# placa_4sensores_Certa.net
KiCad netlist of a schematic drawn in EAGLE
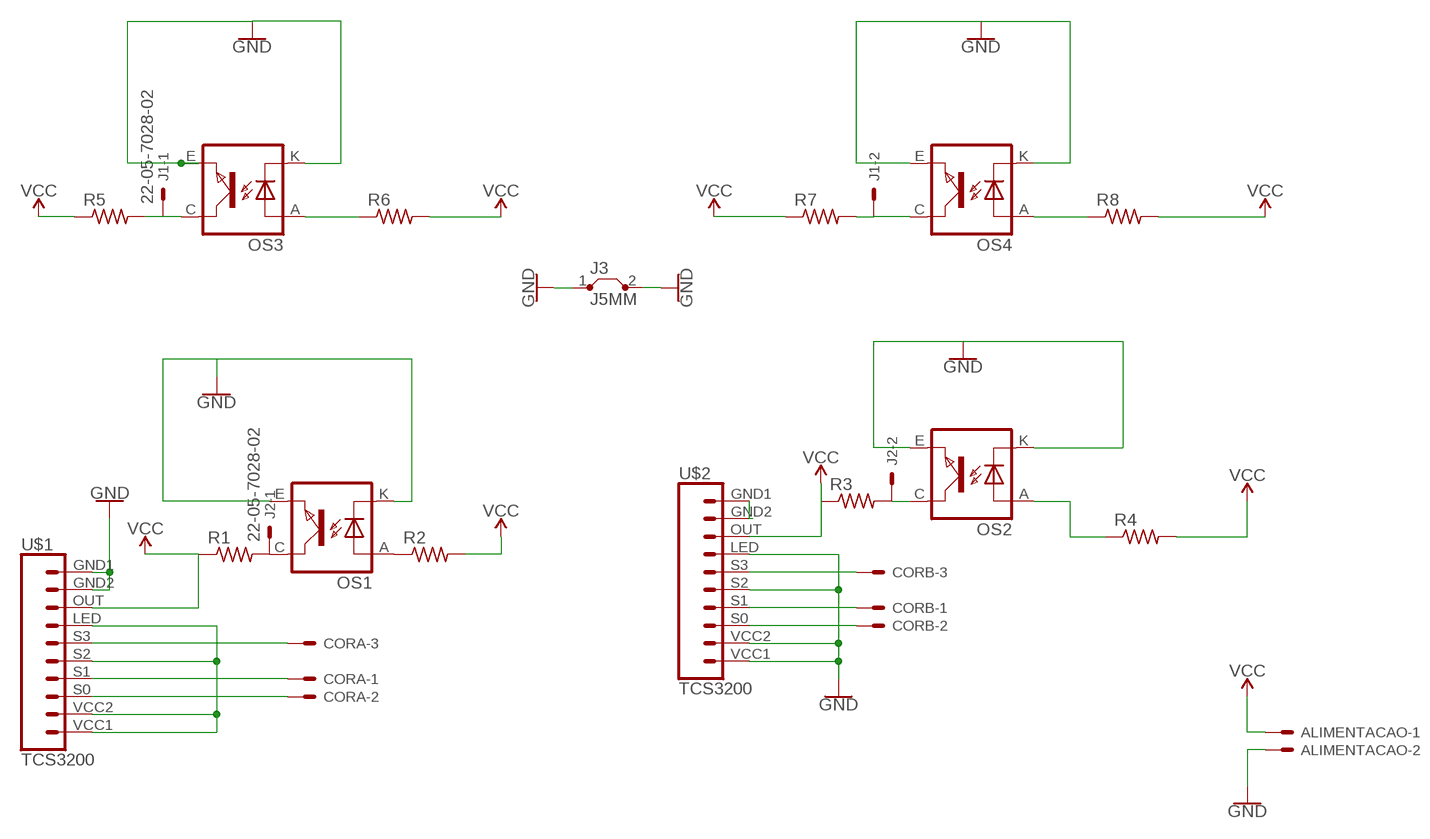
[diagram p0: schematic, sheet 1]

(export (version "E")
  (design (tool "Eeschema 10.0.6"))
  (components
    (comp (ref "ALIMENTACAO")
      (value "22-05-7028-02")
      (footprint "eagle-import:7395-02")
      (libsource (lib "eagle-import") (part "22-?-0205-7028"))
    )
    (comp (ref "CORA")
      (value "22-05-7038-03")
      (footprint "eagle-import:7395-03")
      (libsource (lib "eagle-import") (part "22-?-0305-7038"))
    )
    (comp (ref "CORB")
      (value "22-05-7038-03")
      (footprint "eagle-import:7395-03")
      (libsource (lib "eagle-import") (part "22-?-0305-7038"))
    )
    (comp (ref "J1")
      (value "22-05-7028-02")
      (footprint "eagle-import:7395-02")
      (libsource (lib "eagle-import") (part "22-?-0205-7028"))
    )
    (comp (ref "J2")
      (value "22-05-7028-02")
      (footprint "eagle-import:7395-02")
      (libsource (lib "eagle-import") (part "22-?-0205-7028"))
    )
    (comp (ref "J3")
      (value "J5MM")
      (footprint "eagle-import:05")
      (libsource (lib "eagle-import") (part "J5MM"))
    )
    (comp (ref "OS1")
      (value "TCRT5000")
      (footprint "eagle-import:TCRT5000")
      (libsource (lib "eagle-import") (part "TCRT5000"))
    )
    (comp (ref "OS2")
      (value "TCRT5000")
      (footprint "eagle-import:TCRT5000")
      (libsource (lib "eagle-import") (part "TCRT5000"))
    )
    (comp (ref "OS3")
      (value "TCRT5000")
      (footprint "eagle-import:TCRT5000")
      (libsource (lib "eagle-import") (part "TCRT5000"))
    )
    (comp (ref "OS4")
      (value "TCRT5000")
      (footprint "eagle-import:TCRT5000")
      (libsource (lib "eagle-import") (part "TCRT5000"))
    )
    (comp (ref "R1")
      (value "R-US_0204/5")
      (footprint "eagle-import:0204_5")
      (libsource (lib "eagle-import") (part "R-US_0204/5"))
    )
    (comp (ref "R2")
      (value "R-US_0204/5")
      (footprint "eagle-import:0204_5")
      (libsource (lib "eagle-import") (part "R-US_0204/5"))
    )
    (comp (ref "R3")
      (value "R-US_0204/5")
      (footprint "eagle-import:0204_5")
      (libsource (lib "eagle-import") (part "R-US_0204/5"))
    )
    (comp (ref "R4")
      (value "R-US_0204/5")
      (footprint "eagle-import:0204_5")
      (libsource (lib "eagle-import") (part "R-US_0204/5"))
    )
    (comp (ref "R5")
      (value "R-US_0204/5")
      (footprint "eagle-import:0204_5")
      (libsource (lib "eagle-import") (part "R-US_0204/5"))
    )
    (comp (ref "R6")
      (value "R-US_0204/5")
      (footprint "eagle-import:0204_5")
      (libsource (lib "eagle-import") (part "R-US_0204/5"))
    )
    (comp (ref "R7")
      (value "R-US_0204/5")
      (footprint "eagle-import:0204_5")
      (libsource (lib "eagle-import") (part "R-US_0204/5"))
    )
    (comp (ref "R8")
      (value "R-US_0204/5")
      (footprint "eagle-import:0204_5")
      (libsource (lib "eagle-import") (part "R-US_0204/5"))
    )
    (comp (ref "U$1")
      (value "TCS3200")
      (footprint "eagle-import:TCS3200")
      (libsource (lib "eagle-import") (part "TCS3200"))
    )
    (comp (ref "U$2")
      (value "TCS3200")
      (footprint "eagle-import:TCS3200")
      (libsource (lib "eagle-import") (part "TCS3200"))
    )
  )
  (nets
    (net (code "1") (name "GND") (class "Default")
      (node (ref "ALIMENTACAO") (pin "2") (pinfunction "S_2") (pintype "passive"))
      (node (ref "J3") (pin "1") (pinfunction "1_1") (pintype "passive"))
      (node (ref "J3") (pin "2") (pinfunction "2_2") (pintype "passive"))
      (node (ref "OS1") (pin "E") (pinfunction "EMITTER_E") (pintype "passive"))
      (node (ref "OS1") (pin "K") (pinfunction "CATHODE_K") (pintype "passive"))
      (node (ref "OS2") (pin "E") (pinfunction "EMITTER_E") (pintype "passive"))
      (node (ref "OS2") (pin "K") (pinfunction "CATHODE_K") (pintype "passive"))
      (node (ref "OS3") (pin "E") (pinfunction "EMITTER_E") (pintype "passive"))
      (node (ref "OS3") (pin "K") (pinfunction "CATHODE_K") (pintype "passive"))
      (node (ref "OS4") (pin "E") (pinfunction "EMITTER_E") (pintype "passive"))
      (node (ref "OS4") (pin "K") (pinfunction "CATHODE_K") (pintype "passive"))
      (node (ref "U$1") (pin "GND1") (pinfunction "GND1_GND1") (pintype "passive"))
      (node (ref "U$1") (pin "GND2") (pinfunction "GND2_GND2") (pintype "passive"))
      (node (ref "U$2") (pin "LED") (pinfunction "LED_LED") (pintype "passive"))
      (node (ref "U$2") (pin "S2") (pinfunction "S2_S2") (pintype "passive"))
      (node (ref "U$2") (pin "VCC1") (pinfunction "VCC1_VCC1") (pintype "passive"))
      (node (ref "U$2") (pin "VCC2") (pinfunction "VCC2_VCC2") (pintype "passive"))
    )
    (net (code "2") (name "Net-(CORAA-S)") (class "Default")
      (node (ref "CORA") (pin "1") (pinfunction "S_1") (pintype "passive"))
      (node (ref "U$1") (pin "S1") (pinfunction "S1_S1") (pintype "passive"))
    )
    (net (code "3") (name "Net-(CORAB-S)") (class "Default")
      (node (ref "CORA") (pin "2") (pinfunction "S_2") (pintype "passive"))
      (node (ref "U$1") (pin "S0") (pinfunction "S0_S0") (pintype "passive"))
    )
    (net (code "4") (name "Net-(CORAC-S)") (class "Default")
      (node (ref "CORA") (pin "3") (pinfunction "S_3") (pintype "passive"))
      (node (ref "U$1") (pin "S3") (pinfunction "S3_S3") (pintype "passive"))
    )
    (net (code "5") (name "Net-(CORBA-S)") (class "Default")
      (node (ref "CORB") (pin "1") (pinfunction "S_1") (pintype "passive"))
      (node (ref "U$2") (pin "S1") (pinfunction "S1_S1") (pintype "passive"))
    )
    (net (code "6") (name "Net-(CORBB-S)") (class "Default")
      (node (ref "CORB") (pin "2") (pinfunction "S_2") (pintype "passive"))
      (node (ref "U$2") (pin "S0") (pinfunction "S0_S0") (pintype "passive"))
    )
    (net (code "7") (name "Net-(CORBC-S)") (class "Default")
      (node (ref "CORB") (pin "3") (pinfunction "S_3") (pintype "passive"))
      (node (ref "U$2") (pin "S3") (pinfunction "S3_S3") (pintype "passive"))
    )
    (net (code "8") (name "Net-(J1A-S)") (class "Default")
      (node (ref "J1") (pin "1") (pinfunction "S_1") (pintype "passive"))
      (node (ref "OS3") (pin "C") (pinfunction "COLLECTOR_C") (pintype "passive"))
      (node (ref "R5") (pin "2") (pinfunction "2_2") (pintype "passive"))
    )
    (net (code "9") (name "Net-(J1B-S)") (class "Default")
      (node (ref "J1") (pin "2") (pinfunction "S_2") (pintype "passive"))
      (node (ref "OS4") (pin "C") (pinfunction "COLLECTOR_C") (pintype "passive"))
      (node (ref "R7") (pin "2") (pinfunction "2_2") (pintype "passive"))
    )
    (net (code "10") (name "Net-(J2A-S)") (class "Default")
      (node (ref "J2") (pin "1") (pinfunction "S_1") (pintype "passive"))
      (node (ref "OS1") (pin "C") (pinfunction "COLLECTOR_C") (pintype "passive"))
      (node (ref "R1") (pin "2") (pinfunction "2_2") (pintype "passive"))
    )
    (net (code "11") (name "Net-(J2B-S)") (class "Default")
      (node (ref "J2") (pin "2") (pinfunction "S_2") (pintype "passive"))
      (node (ref "OS2") (pin "C") (pinfunction "COLLECTOR_C") (pintype "passive"))
      (node (ref "R3") (pin "2") (pinfunction "2_2") (pintype "passive"))
    )
    (net (code "12") (name "Net-(OS1-ANODE)") (class "Default")
      (node (ref "OS1") (pin "A") (pinfunction "ANODE_A") (pintype "passive"))
      (node (ref "R2") (pin "1") (pinfunction "1_1") (pintype "passive"))
    )
    (net (code "13") (name "Net-(OS2-ANODE)") (class "Default")
      (node (ref "OS2") (pin "A") (pinfunction "ANODE_A") (pintype "passive"))
      (node (ref "R4") (pin "1") (pinfunction "1_1") (pintype "passive"))
    )
    (net (code "14") (name "Net-(OS3-ANODE)") (class "Default")
      (node (ref "OS3") (pin "A") (pinfunction "ANODE_A") (pintype "passive"))
      (node (ref "R6") (pin "1") (pinfunction "1_1") (pintype "passive"))
    )
    (net (code "15") (name "Net-(OS4-ANODE)") (class "Default")
      (node (ref "OS4") (pin "A") (pinfunction "ANODE_A") (pintype "passive"))
      (node (ref "R8") (pin "1") (pinfunction "1_1") (pintype "passive"))
    )
    (net (code "16") (name "Net-(U$1-PadLED)") (class "Default")
      (node (ref "U$1") (pin "LED") (pinfunction "LED_LED") (pintype "passive"))
      (node (ref "U$1") (pin "S2") (pinfunction "S2_S2") (pintype "passive"))
      (node (ref "U$1") (pin "VCC1") (pinfunction "VCC1_VCC1") (pintype "passive"))
      (node (ref "U$1") (pin "VCC2") (pinfunction "VCC2_VCC2") (pintype "passive"))
    )
    (net (code "17") (name "VCC") (class "Default")
      (node (ref "ALIMENTACAO") (pin "1") (pinfunction "S_1") (pintype "passive"))
      (node (ref "R1") (pin "1") (pinfunction "1_1") (pintype "passive"))
      (node (ref "R2") (pin "2") (pinfunction "2_2") (pintype "passive"))
      (node (ref "R3") (pin "1") (pinfunction "1_1") (pintype "passive"))
      (node (ref "R4") (pin "2") (pinfunction "2_2") (pintype "passive"))
      (node (ref "R5") (pin "1") (pinfunction "1_1") (pintype "passive"))
      (node (ref "R6") (pin "2") (pinfunction "2_2") (pintype "passive"))
      (node (ref "R7") (pin "1") (pinfunction "1_1") (pintype "passive"))
      (node (ref "R8") (pin "2") (pinfunction "2_2") (pintype "passive"))
      (node (ref "U$1") (pin "OUT") (pinfunction "OUT_OUT") (pintype "passive"))
      (node (ref "U$2") (pin "OUT") (pinfunction "OUT_OUT") (pintype "passive"))
    )
    (net (code "18") (name "unconnected-(U$2-PadGND1)") (class "Default")
      (node (ref "U$2") (pin "GND1") (pinfunction "GND1_GND1") (pintype "passive"))
    )
    (net (code "19") (name "unconnected-(U$2-PadGND2)") (class "Default")
      (node (ref "U$2") (pin "GND2") (pinfunction "GND2_GND2") (pintype "passive"))
    )
  )
)
